# tlacitka.net
KiCad netlist of a schematic drawn in EAGLE
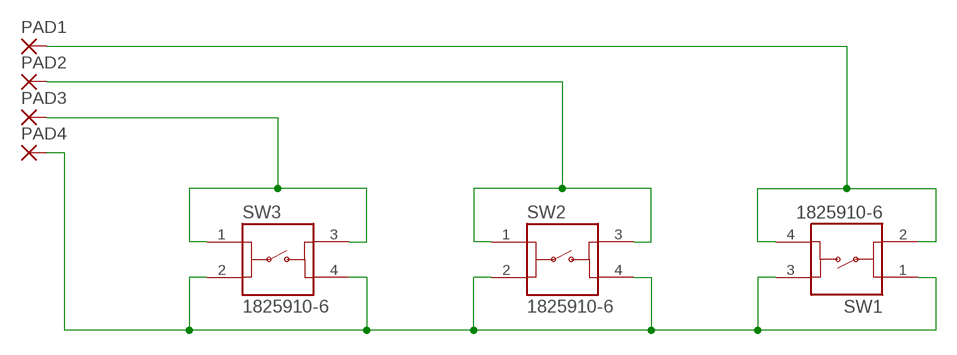
[diagram p0: schematic, sheet 1]

(export (version "E")
  (design (tool "Eeschema 10.0.6"))
  (components
    (comp (ref "PAD1")
      (value "SMD5")
      (footprint "eagle-import:SMD2,54-5,08")
      (libsource (lib "eagle-import") (part "SMD5"))
    )
    (comp (ref "PAD2")
      (value "SMD5")
      (footprint "eagle-import:SMD2,54-5,08")
      (libsource (lib "eagle-import") (part "SMD5"))
    )
    (comp (ref "PAD3")
      (value "SMD5")
      (footprint "eagle-import:SMD2,54-5,08")
      (libsource (lib "eagle-import") (part "SMD5"))
    )
    (comp (ref "PAD4")
      (value "SMD5")
      (footprint "eagle-import:SMD2,54-5,08")
      (libsource (lib "eagle-import") (part "SMD5"))
    )
    (comp (ref "SW1")
      (value "1825910-6")
      (footprint "eagle-import:1825910-6")
      (fields
        (field (name "DIGIKEY_PART_NUMBER") "450-1650-ND")
        (field (name "MANUFACTURER") "TE Connectivity ALCOSWITCH Switches")
        (field (name "CREATED_BY") " PCBLayout.com")
      )
      (libsource (lib "eagle-import") (part "1825910-6"))
    )
    (comp (ref "SW2")
      (value "1825910-6")
      (footprint "eagle-import:1825910-6")
      (fields
        (field (name "DIGIKEY_PART_NUMBER") "450-1650-ND")
        (field (name "MANUFACTURER") "TE Connectivity ALCOSWITCH Switches")
        (field (name "CREATED_BY") " PCBLayout.com")
      )
      (libsource (lib "eagle-import") (part "1825910-6"))
    )
    (comp (ref "SW3")
      (value "1825910-6")
      (footprint "eagle-import:1825910-6")
      (fields
        (field (name "DIGIKEY_PART_NUMBER") "450-1650-ND")
        (field (name "MANUFACTURER") "TE Connectivity ALCOSWITCH Switches")
        (field (name "CREATED_BY") " PCBLayout.com")
      )
      (libsource (lib "eagle-import") (part "1825910-6"))
    )
  )
  (nets
    (net (code "1") (name "Net-(PAD1-P)") (class "Default")
      (node (ref "PAD1") (pin "1") (pinfunction "P_1") (pintype "passive"))
      (node (ref "SW1") (pin "2") (pinfunction "2_2") (pintype "passive"))
      (node (ref "SW1") (pin "4") (pinfunction "4_4") (pintype "passive"))
    )
    (net (code "2") (name "Net-(PAD2-P)") (class "Default")
      (node (ref "PAD2") (pin "1") (pinfunction "P_1") (pintype "passive"))
      (node (ref "SW2") (pin "1") (pinfunction "1_1") (pintype "passive"))
      (node (ref "SW2") (pin "3") (pinfunction "3_3") (pintype "passive"))
    )
    (net (code "3") (name "Net-(PAD3-P)") (class "Default")
      (node (ref "PAD3") (pin "1") (pinfunction "P_1") (pintype "passive"))
      (node (ref "SW3") (pin "1") (pinfunction "1_1") (pintype "passive"))
      (node (ref "SW3") (pin "3") (pinfunction "3_3") (pintype "passive"))
    )
    (net (code "4") (name "Net-(PAD4-P)") (class "Default")
      (node (ref "PAD4") (pin "1") (pinfunction "P_1") (pintype "passive"))
      (node (ref "SW1") (pin "1") (pinfunction "1_1") (pintype "passive"))
      (node (ref "SW1") (pin "3") (pinfunction "3_3") (pintype "passive"))
      (node (ref "SW2") (pin "2") (pinfunction "2_2") (pintype "passive"))
      (node (ref "SW2") (pin "4") (pinfunction "4_4") (pintype "passive"))
      (node (ref "SW3") (pin "2") (pinfunction "2_2") (pintype "passive"))
      (node (ref "SW3") (pin "4") (pinfunction "4_4") (pintype "passive"))
    )
  )
)
